# OpenBook_Schematic.net
KiCad netlist of a schematic drawn in EAGLE
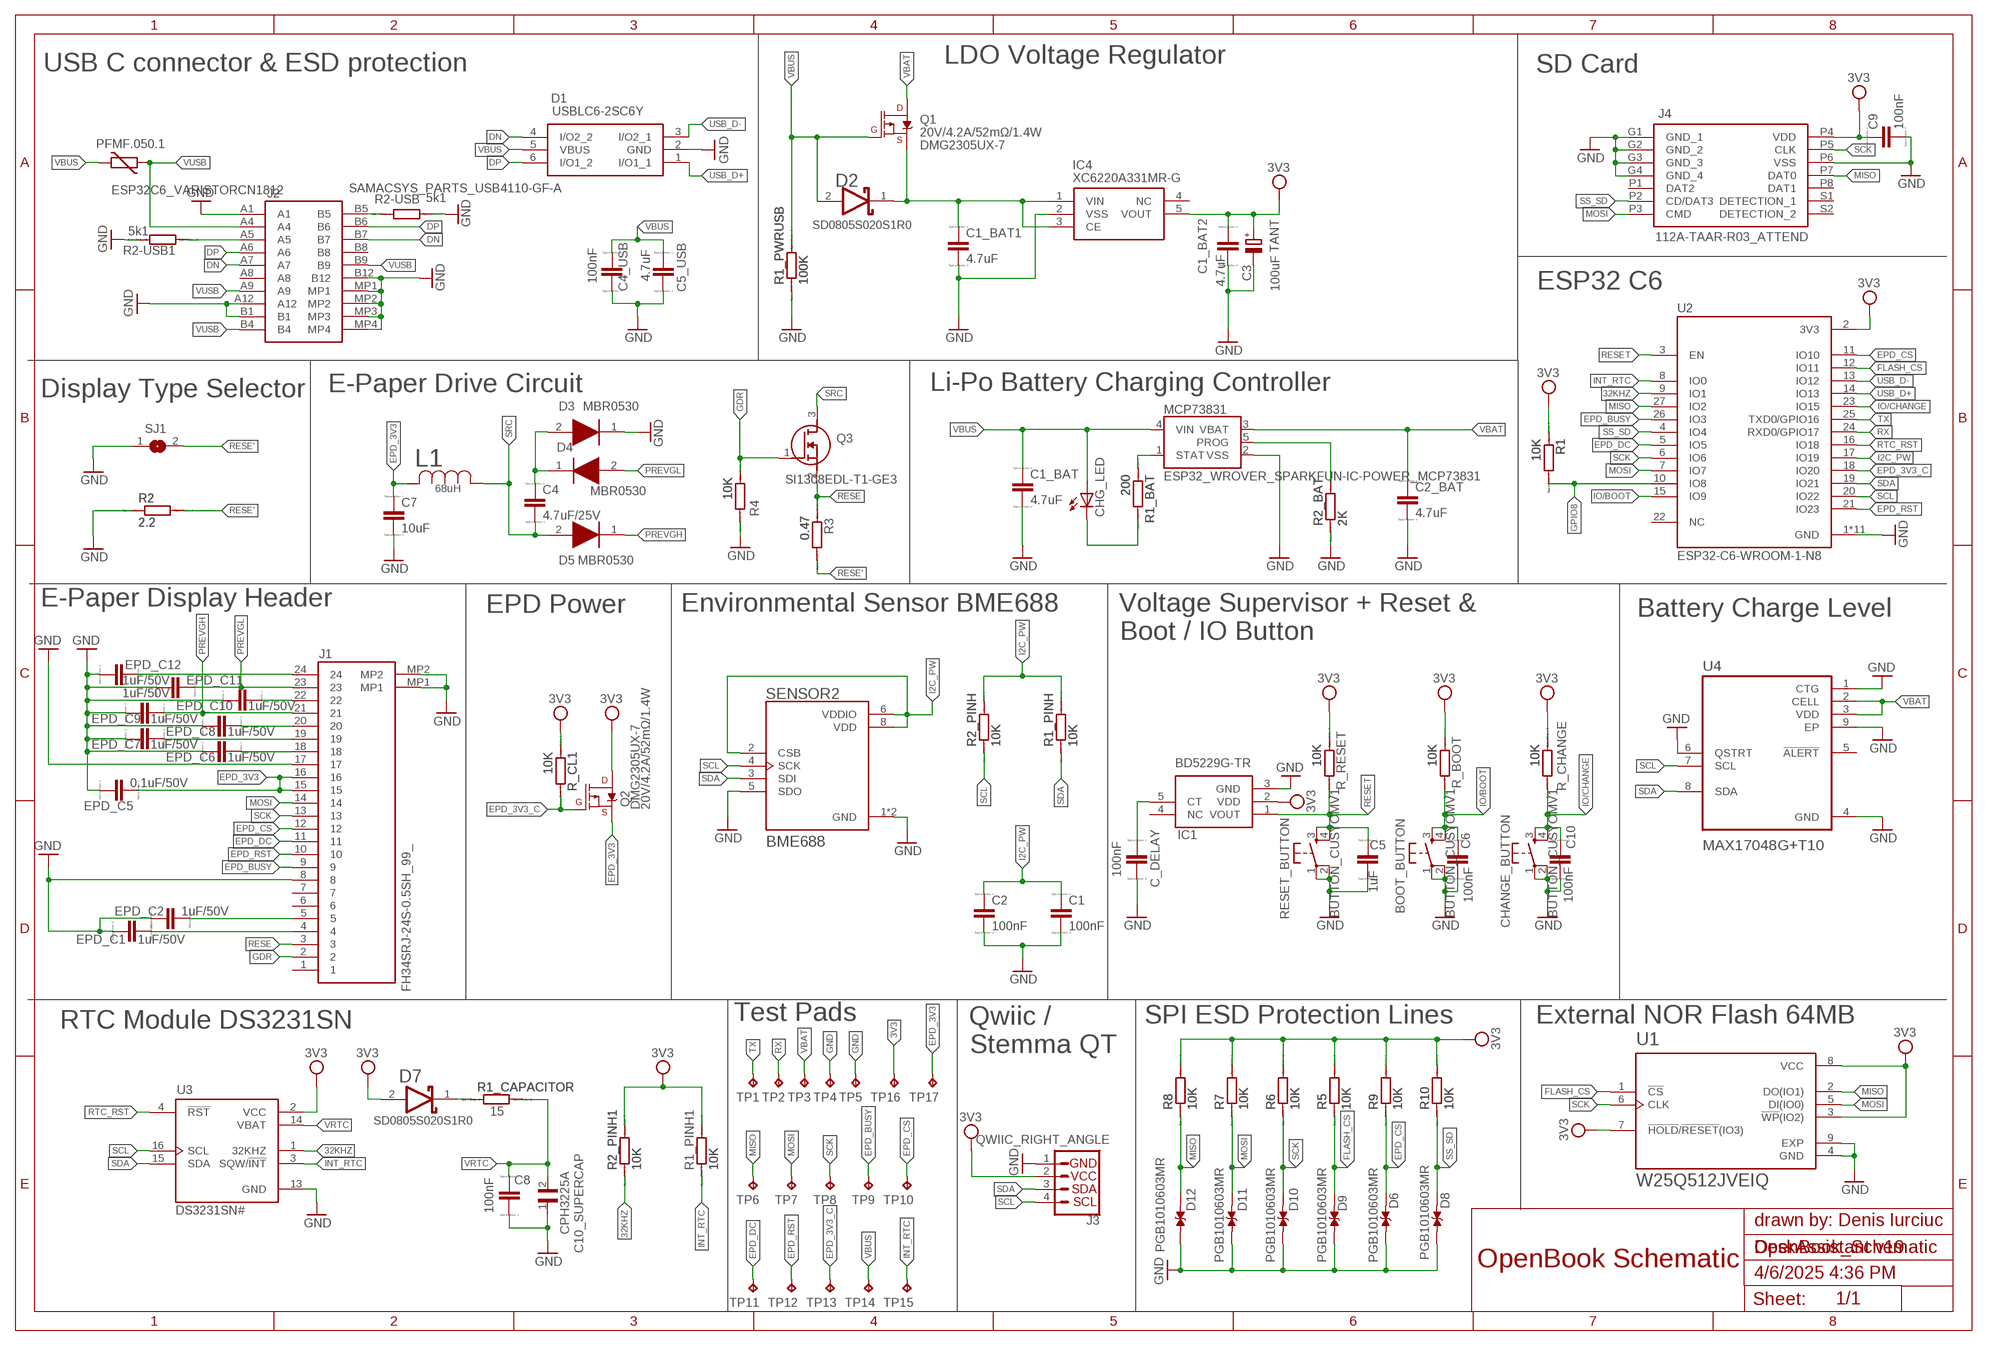
[diagram p0: schematic, sheet 1]

(export (version "E")
  (design (tool "Eeschema 10.0.6"))
  (components
    (comp (ref "BOOT_BUTTON")
      (value "BUTTON_CUSYOMV1")
      (footprint "eagle-import:MYBUTTON")
      (libsource (lib "eagle-import") (part "BUTTON_CUSYOMV1"))
    )
    (comp (ref "C1")
      (value "100nF")
      (footprint "eagle-import:ESP32_WROVER_EAGLE-LTSPICE_C0402")
      (libsource (lib "eagle-import") (part "ESP32_WROVER_EAGLE-LTSPICE_CC0402"))
    )
    (comp (ref "C1_BAT")
      (value "4.7uF")
      (footprint "eagle-import:ESP32_WROVER_EAGLE-LTSPICE_C0402")
      (libsource (lib "eagle-import") (part "ESP32_WROVER_EAGLE-LTSPICE_CC0402"))
    )
    (comp (ref "C1_BAT1")
      (value "4.7uF")
      (footprint "eagle-import:ESP32_WROVER_EAGLE-LTSPICE_C0402")
      (libsource (lib "eagle-import") (part "ESP32_WROVER_EAGLE-LTSPICE_CC0402"))
    )
    (comp (ref "C1_BAT2")
      (value "4.7uF")
      (footprint "eagle-import:ESP32_WROVER_EAGLE-LTSPICE_C0402")
      (libsource (lib "eagle-import") (part "ESP32_WROVER_EAGLE-LTSPICE_CC0402"))
    )
    (comp (ref "C2")
      (value "100nF")
      (footprint "eagle-import:ESP32_WROVER_EAGLE-LTSPICE_C0402")
      (libsource (lib "eagle-import") (part "ESP32_WROVER_EAGLE-LTSPICE_CC0402"))
    )
    (comp (ref "C2_BAT")
      (value "4.7uF")
      (footprint "eagle-import:ESP32_WROVER_EAGLE-LTSPICE_C0402")
      (libsource (lib "eagle-import") (part "ESP32_WROVER_EAGLE-LTSPICE_CC0402"))
    )
    (comp (ref "C3")
      (value "100uF")
      (footprint "eagle-import:RCL_CT3528")
      (fields (field (name "TYPE") "TANT"))
      (libsource (lib "eagle-import") (part "RCL_CPOL-EUCT3528"))
    )
    (comp (ref "C4")
      (value "4.7uF/25V")
      (footprint "eagle-import:ESP32_WROVER_EAGLE-LTSPICE_C0402")
      (libsource (lib "eagle-import") (part "ESP32_WROVER_EAGLE-LTSPICE_CC0402"))
    )
    (comp (ref "C4_USB")
      (value "100nF")
      (footprint "eagle-import:ESP32_WROVER_EAGLE-LTSPICE_C0402")
      (libsource (lib "eagle-import") (part "ESP32_WROVER_EAGLE-LTSPICE_CC0402"))
    )
    (comp (ref "C5")
      (value "1uF")
      (footprint "eagle-import:ESP32_WROVER_EAGLE-LTSPICE_C0402")
      (libsource (lib "eagle-import") (part "ESP32_WROVER_EAGLE-LTSPICE_CC0402"))
    )
    (comp (ref "C5_USB")
      (value "4.7uF")
      (footprint "eagle-import:ESP32_WROVER_EAGLE-LTSPICE_C0402")
      (libsource (lib "eagle-import") (part "ESP32_WROVER_EAGLE-LTSPICE_CC0402"))
    )
    (comp (ref "C6")
      (value "100nF")
      (footprint "eagle-import:ESP32_WROVER_EAGLE-LTSPICE_C0402")
      (libsource (lib "eagle-import") (part "ESP32_WROVER_EAGLE-LTSPICE_CC0402"))
    )
    (comp (ref "C7")
      (value "10uF")
      (footprint "eagle-import:ESP32_WROVER_EAGLE-LTSPICE_C0402")
      (libsource (lib "eagle-import") (part "ESP32_WROVER_EAGLE-LTSPICE_CC0402"))
    )
    (comp (ref "C8")
      (value "100nF")
      (footprint "eagle-import:ESP32_WROVER_EAGLE-LTSPICE_C0402")
      (libsource (lib "eagle-import") (part "ESP32_WROVER_EAGLE-LTSPICE_CC0402"))
    )
    (comp (ref "C9")
      (value "100nF")
      (footprint "eagle-import:ESP32_WROVER_EAGLE-LTSPICE_C0402")
      (libsource (lib "eagle-import") (part "ESP32_WROVER_EAGLE-LTSPICE_CC0402"))
    )
    (comp (ref "C10")
      (value "100nF")
      (footprint "eagle-import:ESP32_WROVER_EAGLE-LTSPICE_C0402")
      (libsource (lib "eagle-import") (part "ESP32_WROVER_EAGLE-LTSPICE_CC0402"))
    )
    (comp (ref "C10_SUPERCAP")
      (value "CPH3225A")
      (footprint "eagle-import:CAPCP3225X100N")
      (fields (field (name "MF") "Seiko Instruments"))
      (libsource (lib "eagle-import") (part "CPH3225A"))
    )
    (comp (ref "CHANGE_BUTTON")
      (value "BUTTON_CUSYOMV1")
      (footprint "eagle-import:MYBUTTON")
      (libsource (lib "eagle-import") (part "BUTTON_CUSYOMV1"))
    )
    (comp (ref "CHG_LED")
      (value "ADAFRUIT_LEDCHIP-LED0603")
      (footprint "eagle-import:ADAFRUIT_CHIP-LED0603")
      (libsource (lib "eagle-import") (part "ADAFRUIT_LEDCHIP-LED0603"))
    )
    (comp (ref "C_DELAY")
      (value "100nF")
      (footprint "eagle-import:ESP32_WROVER_EAGLE-LTSPICE_C0402")
      (libsource (lib "eagle-import") (part "ESP32_WROVER_EAGLE-LTSPICE_CC0402"))
    )
    (comp (ref "D1")
      (value "USBLC6-2SC6Y")
      (footprint "eagle-import:SOT95P280X145-6N")
      (fields (field (name "MF") "STMicroelectronics"))
      (libsource (lib "eagle-import") (part "USBLC6-2SC6Y"))
    )
    (comp (ref "D2")
      (value "ESP32_WROVER_AVX---SD0805S020S1R0_AVX_SD0805S020S1R0_0_0AVX_SD0805S020S1R0_0_0")
      (footprint "eagle-import:ESP32_WROVER_AVX---SD0805S020S1R0_AVX_SD0805S020S1R0_0")
      (fields
        (field (name "DIGIKEY_PART_NUMBER") "478-7800-1-ND")
        (field (name "MF") "AVX")
        (field (name "MOUSER_PART_NUMBER") "581-SD0805S020S1R0")
        (field (name "VALUE_TXT") "SD0805S020S1R0")
      )
      (libsource (lib "eagle-import") (part "ESP32_WROVER_AVX---SD0805S020S1R0_AVX_SD0805S020S1R0_0_0AVX_SD0805S020S1R0_0_0"))
    )
    (comp (ref "D3")
      (value "MBR0530")
      (footprint "eagle-import:SOD3716X135N")
      (fields (field (name "MF") "ON Semiconductor"))
      (libsource (lib "eagle-import") (part "MBR0530"))
    )
    (comp (ref "D4")
      (value "MBR0530")
      (footprint "eagle-import:SOD3716X135N")
      (fields (field (name "MF") "ON Semiconductor"))
      (libsource (lib "eagle-import") (part "MBR0530"))
    )
    (comp (ref "D5")
      (value "MBR0530")
      (footprint "eagle-import:SOD3716X135N")
      (fields (field (name "MF") "ON Semiconductor"))
      (libsource (lib "eagle-import") (part "MBR0530"))
    )
    (comp (ref "D6")
      (value "PGB1010603MR")
      (footprint "eagle-import:DIOC1608X36N")
      (fields (field (name "MF") "Littelfuse Inc."))
      (libsource (lib "eagle-import") (part "PGB1010603MR"))
    )
    (comp (ref "D7")
      (value "SD0805S020S1R0")
      (footprint "eagle-import:ESP32_WROVER_AVX---SD0805S020S1R0_AVX_SD0805S020S1R0_0")
      (fields
        (field (name "DIGIKEY_PART_NUMBER") "478-7800-1-ND")
        (field (name "MF") "AVX")
        (field (name "MOUSER_PART_NUMBER") "581-SD0805S020S1R0")
        (field (name "VALUE_TXT") "SD0805S020S1R0")
      )
      (libsource (lib "eagle-import") (part "ESP32_WROVER_AVX---SD0805S020S1R0_AVX_SD0805S020S1R0_0_0AVX_SD0805S020S1R0_0_0"))
    )
    (comp (ref "D8")
      (value "PGB1010603MR")
      (footprint "eagle-import:DIOC1608X36N")
      (fields (field (name "MF") "Littelfuse Inc."))
      (libsource (lib "eagle-import") (part "PGB1010603MR"))
    )
    (comp (ref "D9")
      (value "PGB1010603MR")
      (footprint "eagle-import:DIOC1608X36N")
      (fields (field (name "MF") "Littelfuse Inc."))
      (libsource (lib "eagle-import") (part "PGB1010603MR"))
    )
    (comp (ref "D10")
      (value "PGB1010603MR")
      (footprint "eagle-import:DIOC1608X36N")
      (fields (field (name "MF") "Littelfuse Inc."))
      (libsource (lib "eagle-import") (part "PGB1010603MR"))
    )
    (comp (ref "D11")
      (value "PGB1010603MR")
      (footprint "eagle-import:DIOC1608X36N")
      (fields (field (name "MF") "Littelfuse Inc."))
      (libsource (lib "eagle-import") (part "PGB1010603MR"))
    )
    (comp (ref "D12")
      (value "PGB1010603MR")
      (footprint "eagle-import:DIOC1608X36N")
      (fields (field (name "MF") "Littelfuse Inc."))
      (libsource (lib "eagle-import") (part "PGB1010603MR"))
    )
    (comp (ref "EPD_C1")
      (value "1uF/50V")
      (footprint "eagle-import:ESP32_WROVER_EAGLE-LTSPICE_C0402")
      (libsource (lib "eagle-import") (part "ESP32_WROVER_EAGLE-LTSPICE_CC0402"))
    )
    (comp (ref "EPD_C2")
      (value "1uF/50V")
      (footprint "eagle-import:ESP32_WROVER_EAGLE-LTSPICE_C0402")
      (libsource (lib "eagle-import") (part "ESP32_WROVER_EAGLE-LTSPICE_CC0402"))
    )
    (comp (ref "EPD_C5")
      (value "0.1uF/50V")
      (footprint "eagle-import:ESP32_WROVER_EAGLE-LTSPICE_C0402")
      (libsource (lib "eagle-import") (part "ESP32_WROVER_EAGLE-LTSPICE_CC0402"))
    )
    (comp (ref "EPD_C6")
      (value "1uF/50V")
      (footprint "eagle-import:ESP32_WROVER_EAGLE-LTSPICE_C0402")
      (libsource (lib "eagle-import") (part "ESP32_WROVER_EAGLE-LTSPICE_CC0402"))
    )
    (comp (ref "EPD_C7")
      (value "1uF/50V")
      (footprint "eagle-import:ESP32_WROVER_EAGLE-LTSPICE_C0402")
      (libsource (lib "eagle-import") (part "ESP32_WROVER_EAGLE-LTSPICE_CC0402"))
    )
    (comp (ref "EPD_C8")
      (value "1uF/50V")
      (footprint "eagle-import:ESP32_WROVER_EAGLE-LTSPICE_C0402")
      (libsource (lib "eagle-import") (part "ESP32_WROVER_EAGLE-LTSPICE_CC0402"))
    )
    (comp (ref "EPD_C9")
      (value "1uF/50V")
      (footprint "eagle-import:ESP32_WROVER_EAGLE-LTSPICE_C0402")
      (libsource (lib "eagle-import") (part "ESP32_WROVER_EAGLE-LTSPICE_CC0402"))
    )
    (comp (ref "EPD_C10")
      (value "1uF/50V")
      (footprint "eagle-import:ESP32_WROVER_EAGLE-LTSPICE_C0402")
      (libsource (lib "eagle-import") (part "ESP32_WROVER_EAGLE-LTSPICE_CC0402"))
    )
    (comp (ref "EPD_C11")
      (value "1uF/50V")
      (footprint "eagle-import:ESP32_WROVER_EAGLE-LTSPICE_C0402")
      (libsource (lib "eagle-import") (part "ESP32_WROVER_EAGLE-LTSPICE_CC0402"))
    )
    (comp (ref "EPD_C12")
      (value "1uF/50V")
      (footprint "eagle-import:ESP32_WROVER_EAGLE-LTSPICE_C0402")
      (libsource (lib "eagle-import") (part "ESP32_WROVER_EAGLE-LTSPICE_CC0402"))
    )
    (comp (ref "IC1")
      (value "BD5229G-TR")
      (footprint "eagle-import:SOT95P280X125-5N")
      (fields (field (name "MOUSER_PART_NUMBER") "755-BD5229G-TR"))
      (libsource (lib "eagle-import") (part "BD5229G-TR"))
    )
    (comp (ref "IC4")
      (value "XC6220A331MR-G")
      (footprint "eagle-import:SOT95P280X120-5N")
      (fields (field (name "MOUSER_PART_NUMBER") "865-XC6220A331MR-G"))
      (libsource (lib "eagle-import") (part "XC6220A331MR-G"))
    )
    (comp (ref "J1")
      (value "FH34SRJ-24S-0.5SH_99_")
      (footprint "eagle-import:FH34SRJ24S05SH99")
      (fields
        (field (name "MANUFACTURER_PART_NUMBER") "FH34SRJ-24S-0.5SH(99)")
        (field (name "MOUSER_PART_NUMBER") "798-FH34SRJ24S05SH99")
      )
      (libsource (lib "eagle-import") (part "FH34SRJ-24S-0.5SH_99_"))
    )
    (comp (ref "J2")
      (value "SAMACSYS_PARTS_USB4110-GF-A")
      (footprint "eagle-import:SAMACSYS_PARTS_USB4110GFA")
      (fields
        (field (name "MANUFACTURER_PART_NUMBER") "USB4110-GF-A")
        (field (name "MOUSER_PART_NUMBER") "640-USB4110-GF-A")
      )
      (libsource (lib "eagle-import") (part "SAMACSYS_PARTS_USB4110-GF-A"))
    )
    (comp (ref "J3")
      (value "QWIIC_RIGHT_ANGLE")
      (footprint "eagle-import:JST04_1MM_RA")
      (libsource (lib "eagle-import") (part "QWIIC_CONNECTORJS-1MM"))
    )
    (comp (ref "J4")
      (value "112A-TAAR-R03_ATTEND")
      (footprint "eagle-import:112ATAARR03ATTEND")
      (fields (field (name "MANUFACTURER_PART_NUMBER") "112A-TAAR-R03 ATTEND"))
      (libsource (lib "eagle-import") (part "112A-TAAR-R03_ATTEND"))
    )
    (comp (ref "L1")
      (value "68uH")
      (footprint "eagle-import:IND_4828-WE-TPC_WRE")
      (fields
        (field (name "MANUFACTURER_PART_NUMBER") "744043680")
        (field (name "COPYRIGHT") "Copyright (C) 2024 Ultra Librarian. All rights reserved.")
      )
      (libsource (lib "eagle-import") (part "744043680IND_4828-WE-TPC_WRE"))
    )
    (comp (ref "MCP73831")
      (value "ESP32_WROVER_SPARKFUN-IC-POWER_MCP73831")
      (footprint "eagle-import:ESP32_WROVER_SPARKFUN-IC-POWER_SOT23-5")
      (libsource (lib "eagle-import") (part "ESP32_WROVER_SPARKFUN-IC-POWER_MCP73831"))
    )
    (comp (ref "PFMF.050.1")
      (value "ESP32C6_VARISTORCN1812")
      (footprint "eagle-import:ESP32C6_VARISTOR_CT_CN1812")
      (libsource (lib "eagle-import") (part "ESP32C6_VARISTORCN1812"))
    )
    (comp (ref "Q1")
      (value "20V/4.2A/52mΩ/1.4W")
      (footprint "eagle-import:ESP32_WROVER_SPARKFUN-DISCRETESEMI_SOT23-3")
      (fields (field (name "P_CHANNEL") "DMG2305UX-7"))
      (libsource (lib "eagle-import") (part "ESP32_WROVER_SPARKFUN-DISCRETESEMI_MOSFET_PCH-DMG2305UX-7"))
    )
    (comp (ref "Q2")
      (value "20V/4.2A/52mΩ/1.4W")
      (footprint "eagle-import:ESP32_WROVER_SPARKFUN-DISCRETESEMI_SOT23-3")
      (fields (field (name "P_CHANNEL") "DMG2305UX-7"))
      (libsource (lib "eagle-import") (part "ESP32_WROVER_SPARKFUN-DISCRETESEMI_MOSFET_PCH-DMG2305UX-7"))
    )
    (comp (ref "Q3")
      (value "SI1308EDL-T1-GE3")
      (footprint "eagle-import:SOT65P210X110-3N")
      (fields (field (name "MF") "Vishay Siliconix"))
      (libsource (lib "eagle-import") (part "SI1308EDL-T1-GE3"))
    )
    (comp (ref "R1")
      (value "10K")
      (footprint "eagle-import:ESP32_WROVER_EAGLE-LTSPICE_R0402")
      (libsource (lib "eagle-import") (part "ESP32_WROVER_EAGLE-LTSPICE_RR0402"))
    )
    (comp (ref "R1_BAT")
      (value "200")
      (footprint "eagle-import:ESP32_WROVER_EAGLE-LTSPICE_R0402")
      (libsource (lib "eagle-import") (part "ESP32_WROVER_EAGLE-LTSPICE_RR0402"))
    )
    (comp (ref "R1_CAPACITOR")
      (value "15")
      (footprint "eagle-import:ESP32_WROVER_EAGLE-LTSPICE_R0402")
      (libsource (lib "eagle-import") (part "ESP32_WROVER_EAGLE-LTSPICE_RR0402"))
    )
    (comp (ref "R1_PINH")
      (value "10K")
      (footprint "eagle-import:ESP32_WROVER_EAGLE-LTSPICE_R0402")
      (libsource (lib "eagle-import") (part "ESP32_WROVER_EAGLE-LTSPICE_RR0402"))
    )
    (comp (ref "R1_PINH1")
      (value "10K")
      (footprint "eagle-import:ESP32_WROVER_EAGLE-LTSPICE_R0402")
      (libsource (lib "eagle-import") (part "ESP32_WROVER_EAGLE-LTSPICE_RR0402"))
    )
    (comp (ref "R1_PWRUSB")
      (value "100K")
      (footprint "eagle-import:ESP32_WROVER_EAGLE-LTSPICE_R0402")
      (libsource (lib "eagle-import") (part "ESP32_WROVER_EAGLE-LTSPICE_RR0402"))
    )
    (comp (ref "R2")
      (value "2.2")
      (footprint "eagle-import:ESP32_WROVER_EAGLE-LTSPICE_R0402")
      (libsource (lib "eagle-import") (part "ESP32_WROVER_EAGLE-LTSPICE_RR0402"))
    )
    (comp (ref "R2-USB")
      (value "5k1")
      (footprint "eagle-import:ESP32_WROVER_EAGLE-LTSPICE_R0402")
      (libsource (lib "eagle-import") (part "ESP32_WROVER_EAGLE-LTSPICE_RR0402"))
    )
    (comp (ref "R2-USB1")
      (value "5k1")
      (footprint "eagle-import:ESP32_WROVER_EAGLE-LTSPICE_R0402")
      (libsource (lib "eagle-import") (part "ESP32_WROVER_EAGLE-LTSPICE_RR0402"))
    )
    (comp (ref "R2_BAT")
      (value "2K")
      (footprint "eagle-import:ESP32_WROVER_EAGLE-LTSPICE_R0402")
      (libsource (lib "eagle-import") (part "ESP32_WROVER_EAGLE-LTSPICE_RR0402"))
    )
    (comp (ref "R2_PINH")
      (value "10K")
      (footprint "eagle-import:ESP32_WROVER_EAGLE-LTSPICE_R0402")
      (libsource (lib "eagle-import") (part "ESP32_WROVER_EAGLE-LTSPICE_RR0402"))
    )
    (comp (ref "R2_PINH1")
      (value "10K")
      (footprint "eagle-import:ESP32_WROVER_EAGLE-LTSPICE_R0402")
      (libsource (lib "eagle-import") (part "ESP32_WROVER_EAGLE-LTSPICE_RR0402"))
    )
    (comp (ref "R3")
      (value "0.47")
      (footprint "eagle-import:ESP32_WROVER_EAGLE-LTSPICE_R0402")
      (libsource (lib "eagle-import") (part "ESP32_WROVER_EAGLE-LTSPICE_RR0402"))
    )
    (comp (ref "R4")
      (value "10K")
      (footprint "eagle-import:ESP32_WROVER_EAGLE-LTSPICE_R0402")
      (libsource (lib "eagle-import") (part "ESP32_WROVER_EAGLE-LTSPICE_RR0402"))
    )
    (comp (ref "R5")
      (value "10K")
      (footprint "eagle-import:ESP32_WROVER_EAGLE-LTSPICE_R0402")
      (libsource (lib "eagle-import") (part "ESP32_WROVER_EAGLE-LTSPICE_RR0402"))
    )
    (comp (ref "R6")
      (value "10K")
      (footprint "eagle-import:ESP32_WROVER_EAGLE-LTSPICE_R0402")
      (libsource (lib "eagle-import") (part "ESP32_WROVER_EAGLE-LTSPICE_RR0402"))
    )
    (comp (ref "R7")
      (value "10K")
      (footprint "eagle-import:ESP32_WROVER_EAGLE-LTSPICE_R0402")
      (libsource (lib "eagle-import") (part "ESP32_WROVER_EAGLE-LTSPICE_RR0402"))
    )
    (comp (ref "R8")
      (value "10K")
      (footprint "eagle-import:ESP32_WROVER_EAGLE-LTSPICE_R0402")
      (libsource (lib "eagle-import") (part "ESP32_WROVER_EAGLE-LTSPICE_RR0402"))
    )
    (comp (ref "R9")
      (value "10K")
      (footprint "eagle-import:ESP32_WROVER_EAGLE-LTSPICE_R0402")
      (libsource (lib "eagle-import") (part "ESP32_WROVER_EAGLE-LTSPICE_RR0402"))
    )
    (comp (ref "R10")
      (value "10K")
      (footprint "eagle-import:ESP32_WROVER_EAGLE-LTSPICE_R0402")
      (libsource (lib "eagle-import") (part "ESP32_WROVER_EAGLE-LTSPICE_RR0402"))
    )
    (comp (ref "RESET_BUTTON")
      (value "BUTTON_CUSYOMV1")
      (footprint "eagle-import:MYBUTTON")
      (libsource (lib "eagle-import") (part "BUTTON_CUSYOMV1"))
    )
    (comp (ref "R_BOOT")
      (value "10K")
      (footprint "eagle-import:ESP32_WROVER_EAGLE-LTSPICE_R0402")
      (libsource (lib "eagle-import") (part "ESP32_WROVER_EAGLE-LTSPICE_RR0402"))
    )
    (comp (ref "R_CHANGE")
      (value "10K")
      (footprint "eagle-import:ESP32_WROVER_EAGLE-LTSPICE_R0402")
      (libsource (lib "eagle-import") (part "ESP32_WROVER_EAGLE-LTSPICE_RR0402"))
    )
    (comp (ref "R_CL1")
      (value "10K")
      (footprint "eagle-import:ESP32_WROVER_EAGLE-LTSPICE_R0402")
      (libsource (lib "eagle-import") (part "ESP32_WROVER_EAGLE-LTSPICE_RR0402"))
    )
    (comp (ref "R_RESET")
      (value "10K")
      (footprint "eagle-import:ESP32_WROVER_EAGLE-LTSPICE_R0402")
      (libsource (lib "eagle-import") (part "ESP32_WROVER_EAGLE-LTSPICE_RR0402"))
    )
    (comp (ref "SENSOR2")
      (value "BME688")
      (footprint "eagle-import:ESP32_WROVER_BME680_PSON80P300X300X100-8N")
      (fields (field (name "MF") "Bosch Sensortec") (field (name "MP") "BME680"))
      (libsource (lib "eagle-import") (part "ESP32_WROVER_BME680_BME680"))
    )
    (comp (ref "SJ1") (value "SJ") (footprint "eagle-import:SJ") (libsource (lib "eagle-import") (part "SJ")))
    (comp (ref "TP1")
      (value "TPTP20R")
      (footprint "eagle-import:TP20R")
      (libsource (lib "eagle-import") (part "TPTP20R"))
    )
    (comp (ref "TP2")
      (value "TPTP20R")
      (footprint "eagle-import:TP20R")
      (libsource (lib "eagle-import") (part "TPTP20R"))
    )
    (comp (ref "TP3")
      (value "TPTP20R")
      (footprint "eagle-import:TP20R")
      (libsource (lib "eagle-import") (part "TPTP20R"))
    )
    (comp (ref "TP4")
      (value "TPTP20R")
      (footprint "eagle-import:TP20R")
      (libsource (lib "eagle-import") (part "TPTP20R"))
    )
    (comp (ref "TP5")
      (value "TPTP20R")
      (footprint "eagle-import:TP20R")
      (libsource (lib "eagle-import") (part "TPTP20R"))
    )
    (comp (ref "TP6")
      (value "TPTP20R")
      (footprint "eagle-import:TP20R")
      (libsource (lib "eagle-import") (part "TPTP20R"))
    )
    (comp (ref "TP7")
      (value "TPTP20R")
      (footprint "eagle-import:TP20R")
      (libsource (lib "eagle-import") (part "TPTP20R"))
    )
    (comp (ref "TP8")
      (value "TPTP20R")
      (footprint "eagle-import:TP20R")
      (libsource (lib "eagle-import") (part "TPTP20R"))
    )
    (comp (ref "TP9")
      (value "TPTP20R")
      (footprint "eagle-import:TP20R")
      (libsource (lib "eagle-import") (part "TPTP20R"))
    )
    (comp (ref "TP10")
      (value "TPTP20R")
      (footprint "eagle-import:TP20R")
      (libsource (lib "eagle-import") (part "TPTP20R"))
    )
    (comp (ref "TP11")
      (value "TPTP20R")
      (footprint "eagle-import:TP20R")
      (libsource (lib "eagle-import") (part "TPTP20R"))
    )
    (comp (ref "TP12")
      (value "TPTP20R")
      (footprint "eagle-import:TP20R")
      (libsource (lib "eagle-import") (part "TPTP20R"))
    )
    (comp (ref "TP13")
      (value "TPTP20R")
      (footprint "eagle-import:TP20R")
      (libsource (lib "eagle-import") (part "TPTP20R"))
    )
    (comp (ref "TP14")
      (value "TPTP20R")
      (footprint "eagle-import:TP20R")
      (libsource (lib "eagle-import") (part "TPTP20R"))
    )
    (comp (ref "TP15")
      (value "TPTP20R")
      (footprint "eagle-import:TP20R")
      (libsource (lib "eagle-import") (part "TPTP20R"))
    )
    (comp (ref "TP16")
      (value "TPTP20R")
      (footprint "eagle-import:TP20R")
      (libsource (lib "eagle-import") (part "TPTP20R"))
    )
    (comp (ref "TP17")
      (value "TPTP20R")
      (footprint "eagle-import:TP20R")
      (libsource (lib "eagle-import") (part "TPTP20R"))
    )
    (comp (ref "U1")
      (value "W25Q512JVEIQ")
      (footprint "eagle-import:SON127P600X800X80-9N")
      (fields (field (name "MF") "Winbond Electronics"))
      (libsource (lib "eagle-import") (part "W25Q512JVEIQ"))
    )
    (comp (ref "U2")
      (value "ESP32-C6-WROOM-1-N8")
      (footprint "eagle-import:XCVR_ESP32-C6-WROOM-1-N8")
      (fields (field (name "MF") "Espressif Systems"))
      (libsource (lib "eagle-import") (part "ESP32-C6-WROOM-1-N8"))
    )
    (comp (ref "U3")
      (value "DS3231SN#")
      (footprint "eagle-import:SOIC127P1032X265-16N")
      (fields (field (name "MF") "Analog Devices"))
      (libsource (lib "eagle-import") (part "DS3231SN#"))
    )
    (comp (ref "U4")
      (value "MAX17048G+T10")
      (footprint "eagle-import:SON50P200X200X80-9N")
      (fields (field (name "MF") "Analog Devices"))
      (libsource (lib "eagle-import") (part "MAX17048G+T10"))
    )
  )
  (nets
    (net (code "1") (name "3V3") (class "Default")
      (node (ref "C1_BAT2") (pin "1") (pinfunction "1_1") (pintype "passive"))
      (node (ref "C3") (pin "+") (pinfunction "+_+") (pintype "passive"))
      (node (ref "C9") (pin "1") (pinfunction "1_1") (pintype "passive"))
      (node (ref "D7") (pin "2") (pinfunction "ANODE_2") (pintype "bidirectional"))
      (node (ref "IC1") (pin "2") (pinfunction "VDD_2") (pintype "bidirectional"))
      (node (ref "IC4") (pin "5") (pinfunction "VOUT_5") (pintype "bidirectional"))
      (node (ref "J3") (pin "2") (pinfunction "2_2") (pintype "power_in"))
      (node (ref "J4") (pin "P4") (pinfunction "VDD_P4") (pintype "bidirectional"))
      (node (ref "Q2") (pin "3") (pinfunction "D_3") (pintype "bidirectional"))
      (node (ref "R1") (pin "1") (pinfunction "1_1") (pintype "passive"))
      (node (ref "R10") (pin "2") (pinfunction "2_2") (pintype "passive"))
      (node (ref "R1_PINH1") (pin "2") (pinfunction "2_2") (pintype "passive"))
      (node (ref "R2_PINH1") (pin "2") (pinfunction "2_2") (pintype "passive"))
      (node (ref "R5") (pin "2") (pinfunction "2_2") (pintype "passive"))
      (node (ref "R6") (pin "2") (pinfunction "2_2") (pintype "passive"))
      (node (ref "R7") (pin "2") (pinfunction "2_2") (pintype "passive"))
      (node (ref "R8") (pin "2") (pinfunction "2_2") (pintype "passive"))
      (node (ref "R9") (pin "2") (pinfunction "2_2") (pintype "passive"))
      (node (ref "R_BOOT") (pin "1") (pinfunction "1_1") (pintype "passive"))
      (node (ref "R_CHANGE") (pin "1") (pinfunction "1_1") (pintype "passive"))
      (node (ref "R_CL1") (pin "1") (pinfunction "1_1") (pintype "passive"))
      (node (ref "R_RESET") (pin "1") (pinfunction "1_1") (pintype "passive"))
      (node (ref "TP16") (pin "TP") (pinfunction "TP_TP") (pintype "input"))
      (node (ref "U1") (pin "3") (pinfunction "~{WP}(IO2)_3") (pintype "bidirectional"))
      (node (ref "U1") (pin "7") (pinfunction "~{HOLD}/~{RESET}(IO3)_7") (pintype "bidirectional"))
      (node (ref "U1") (pin "8") (pinfunction "VCC_8") (pintype "power_in"))
      (node (ref "U2") (pin "2") (pinfunction "3V3_2") (pintype "power_in"))
      (node (ref "U3") (pin "2") (pinfunction "VCC_2") (pintype "power_in"))
    )
    (net (code "2") (name "32KHZ") (class "Default")
      (node (ref "R2_PINH1") (pin "1") (pinfunction "1_1") (pintype "passive"))
      (node (ref "U2") (pin "9") (pinfunction "IO1_9") (pintype "bidirectional"))
      (node (ref "U3") (pin "1") (pinfunction "32KHZ_1") (pintype "output"))
    )
    (net (code "3") (name "DN") (class "Default")
      (node (ref "D1") (pin "4") (pinfunction "I/O2_2_4") (pintype "bidirectional"))
      (node (ref "J2") (pin "A7") (pinfunction "A7_A7") (pintype "bidirectional"))
      (node (ref "J2") (pin "B7") (pinfunction "B7_B7") (pintype "bidirectional"))
    )
    (net (code "4") (name "DP") (class "Default")
      (node (ref "D1") (pin "6") (pinfunction "I/O1_2_6") (pintype "bidirectional"))
      (node (ref "J2") (pin "A6") (pinfunction "A6_A6") (pintype "bidirectional"))
      (node (ref "J2") (pin "B6") (pinfunction "B6_B6") (pintype "bidirectional"))
    )
    (net (code "5") (name "EPD_3V3") (class "Default")
      (node (ref "C7") (pin "1") (pinfunction "1_1") (pintype "passive"))
      (node (ref "EPD_C5") (pin "1") (pinfunction "1_1") (pintype "passive"))
      (node (ref "J1") (pin "15") (pinfunction "15_15") (pintype "bidirectional"))
      (node (ref "J1") (pin "16") (pinfunction "16_16") (pintype "bidirectional"))
      (node (ref "L1") (pin "2") (pinfunction "2_2") (pintype "passive"))
      (node (ref "Q2") (pin "2") (pinfunction "S_2") (pintype "bidirectional"))
      (node (ref "TP17") (pin "TP") (pinfunction "TP_TP") (pintype "input"))
    )
    (net (code "6") (name "EPD_3V3_C") (class "Default")
      (node (ref "Q2") (pin "1") (pinfunction "G_1") (pintype "bidirectional"))
      (node (ref "R_CL1") (pin "2") (pinfunction "2_2") (pintype "passive"))
      (node (ref "TP13") (pin "TP") (pinfunction "TP_TP") (pintype "input"))
      (node (ref "U2") (pin "18") (pinfunction "IO20_18") (pintype "bidirectional"))
    )
    (net (code "7") (name "EPD_BUSY") (class "Default")
      (node (ref "J1") (pin "9") (pinfunction "9_9") (pintype "bidirectional"))
      (node (ref "TP9") (pin "TP") (pinfunction "TP_TP") (pintype "input"))
      (node (ref "U2") (pin "26") (pinfunction "IO3_26") (pintype "bidirectional"))
    )
    (net (code "8") (name "EPD_CS") (class "Default")
      (node (ref "D6") (pin "2") (pinfunction "2_2") (pintype "passive"))
      (node (ref "J1") (pin "12") (pinfunction "12_12") (pintype "bidirectional"))
      (node (ref "R9") (pin "1") (pinfunction "1_1") (pintype "passive"))
      (node (ref "TP10") (pin "TP") (pinfunction "TP_TP") (pintype "input"))
      (node (ref "U2") (pin "11") (pinfunction "IO10_11") (pintype "bidirectional"))
    )
    (net (code "9") (name "EPD_DC") (class "Default")
      (node (ref "J1") (pin "11") (pinfunction "11_11") (pintype "bidirectional"))
      (node (ref "TP11") (pin "TP") (pinfunction "TP_TP") (pintype "input"))
      (node (ref "U2") (pin "5") (pinfunction "IO5_5") (pintype "bidirectional"))
    )
    (net (code "10") (name "EPD_RST") (class "Default")
      (node (ref "J1") (pin "10") (pinfunction "10_10") (pintype "bidirectional"))
      (node (ref "TP12") (pin "TP") (pinfunction "TP_TP") (pintype "input"))
      (node (ref "U2") (pin "21") (pinfunction "IO23_21") (pintype "bidirectional"))
    )
    (net (code "11") (name "FLASH_CS") (class "Default")
      (node (ref "D9") (pin "2") (pinfunction "2_2") (pintype "passive"))
      (node (ref "R5") (pin "1") (pinfunction "1_1") (pintype "passive"))
      (node (ref "U1") (pin "1") (pinfunction "~{CS}_1") (pintype "input"))
      (node (ref "U2") (pin "12") (pinfunction "IO11_12") (pintype "bidirectional"))
    )
    (net (code "12") (name "GDR") (class "Default")
      (node (ref "J1") (pin "2") (pinfunction "2_2") (pintype "bidirectional"))
      (node (ref "Q3") (pin "1") (pinfunction "G_1") (pintype "bidirectional"))
      (node (ref "R4") (pin "1") (pinfunction "1_1") (pintype "passive"))
    )
    (net (code "13") (name "GND") (class "Default")
      (node (ref "BOOT_BUTTON") (pin "1") (pinfunction "1_1") (pintype "passive"))
      (node (ref "BOOT_BUTTON") (pin "2") (pinfunction "2_2") (pintype "passive"))
      (node (ref "C1") (pin "2") (pinfunction "2_2") (pintype "passive"))
      (node (ref "C10") (pin "2") (pinfunction "2_2") (pintype "passive"))
      (node (ref "C10_SUPERCAP") (pin "1") (pinfunction "1_1") (pintype "passive"))
      (node (ref "C1_BAT") (pin "2") (pinfunction "2_2") (pintype "passive"))
      (node (ref "C1_BAT1") (pin "2") (pinfunction "2_2") (pintype "passive"))
      (node (ref "C1_BAT2") (pin "2") (pinfunction "2_2") (pintype "passive"))
      (node (ref "C2") (pin "2") (pinfunction "2_2") (pintype "passive"))
      (node (ref "C2_BAT") (pin "2") (pinfunction "2_2") (pintype "passive"))
      (node (ref "C3") (pin "-") (pinfunction "-_-") (pintype "passive"))
      (node (ref "C4_USB") (pin "2") (pinfunction "2_2") (pintype "passive"))
      (node (ref "C5") (pin "2") (pinfunction "2_2") (pintype "passive"))
      (node (ref "C5_USB") (pin "2") (pinfunction "2_2") (pintype "passive"))
      (node (ref "C6") (pin "2") (pinfunction "2_2") (pintype "passive"))
      (node (ref "C7") (pin "2") (pinfunction "2_2") (pintype "passive"))
      (node (ref "C8") (pin "2") (pinfunction "2_2") (pintype "passive"))
      (node (ref "C9") (pin "2") (pinfunction "2_2") (pintype "passive"))
      (node (ref "CHANGE_BUTTON") (pin "1") (pinfunction "1_1") (pintype "passive"))
      (node (ref "CHANGE_BUTTON") (pin "2") (pinfunction "2_2") (pintype "passive"))
      (node (ref "C_DELAY") (pin "2") (pinfunction "2_2") (pintype "passive"))
      (node (ref "D1") (pin "2") (pinfunction "GND_2") (pintype "bidirectional"))
      (node (ref "D10") (pin "1") (pinfunction "1_1") (pintype "passive"))
      (node (ref "D11") (pin "1") (pinfunction "1_1") (pintype "passive"))
      (node (ref "D12") (pin "1") (pinfunction "1_1") (pintype "passive"))
      (node (ref "D3") (pin "1") (pinfunction "K_1") (pintype "bidirectional"))
      (node (ref "D6") (pin "1") (pinfunction "1_1") (pintype "passive"))
      (node (ref "D8") (pin "1") (pinfunction "1_1") (pintype "passive"))
      (node (ref "D9") (pin "1") (pinfunction "1_1") (pintype "passive"))
      (node (ref "EPD_C1") (pin "2") (pinfunction "2_2") (pintype "passive"))
      (node (ref "EPD_C10") (pin "2") (pinfunction "2_2") (pintype "passive"))
      (node (ref "EPD_C11") (pin "2") (pinfunction "2_2") (pintype "passive"))
      (node (ref "EPD_C12") (pin "2") (pinfunction "2_2") (pintype "passive"))
      (node (ref "EPD_C2") (pin "2") (pinfunction "2_2") (pintype "passive"))
      (node (ref "EPD_C5") (pin "2") (pinfunction "2_2") (pintype "passive"))
      (node (ref "EPD_C6") (pin "2") (pinfunction "2_2") (pintype "passive"))
      (node (ref "EPD_C7") (pin "2") (pinfunction "2_2") (pintype "passive"))
      (node (ref "EPD_C8") (pin "2") (pinfunction "2_2") (pintype "passive"))
      (node (ref "EPD_C9") (pin "2") (pinfunction "2_2") (pintype "passive"))
      (node (ref "IC1") (pin "3") (pinfunction "GND_3") (pintype "bidirectional"))
      (node (ref "IC4") (pin "2") (pinfunction "VSS_2") (pintype "bidirectional"))
      (node (ref "J1") (pin "17") (pinfunction "17_17") (pintype "bidirectional"))
      (node (ref "J1") (pin "8") (pinfunction "8_8") (pintype "bidirectional"))
      (node (ref "J1") (pin "MP1") (pinfunction "MP1_MP1") (pintype "bidirectional"))
      (node (ref "J1") (pin "MP2") (pinfunction "MP2_MP2") (pintype "bidirectional"))
      (node (ref "J2") (pin "A1") (pinfunction "A1_A1") (pintype "bidirectional"))
      (node (ref "J2") (pin "A12") (pinfunction "A12_A12") (pintype "bidirectional"))
      (node (ref "J2") (pin "B1") (pinfunction "B1_B1") (pintype "bidirectional"))
      (node (ref "J2") (pin "B12") (pinfunction "B12_B12") (pintype "bidirectional"))
      (node (ref "J2") (pin "MP1") (pinfunction "MP1_MP1") (pintype "bidirectional"))
      (node (ref "J2") (pin "MP2") (pinfunction "MP2_MP2") (pintype "bidirectional"))
      (node (ref "J2") (pin "MP3") (pinfunction "MP3_MP3") (pintype "bidirectional"))
      (node (ref "J2") (pin "MP4") (pinfunction "MP4_MP4") (pintype "bidirectional"))
      (node (ref "J3") (pin "1") (pinfunction "1_1") (pintype "power_in"))
      (node (ref "J4") (pin "G1") (pinfunction "GND_1_G1") (pintype "bidirectional"))
      (node (ref "J4") (pin "G2") (pinfunction "GND_2_G2") (pintype "bidirectional"))
      (node (ref "J4") (pin "G3") (pinfunction "GND_3_G3") (pintype "bidirectional"))
      (node (ref "J4") (pin "G4") (pinfunction "GND_4_G4") (pintype "bidirectional"))
      (node (ref "J4") (pin "P6") (pinfunction "VSS_P6") (pintype "bidirectional"))
      (node (ref "MCP73831") (pin "2") (pinfunction "VSS_2") (pintype "power_in"))
      (node (ref "R1_PWRUSB") (pin "1") (pinfunction "1_1") (pintype "passive"))
      (node (ref "R2") (pin "1") (pinfunction "1_1") (pintype "passive"))
      (node (ref "R2-USB") (pin "2") (pinfunction "2_2") (pintype "passive"))
      (node (ref "R2-USB1") (pin "1") (pinfunction "1_1") (pintype "passive"))
      (node (ref "R2_BAT") (pin "1") (pinfunction "1_1") (pintype "passive"))
      (node (ref "R4") (pin "2") (pinfunction "2_2") (pintype "passive"))
      (node (ref "RESET_BUTTON") (pin "1") (pinfunction "1_1") (pintype "passive"))
      (node (ref "RESET_BUTTON") (pin "2") (pinfunction "2_2") (pintype "passive"))
      (node (ref "SENSOR2") (pin "1") (pinfunction "GND_1") (pintype "power_in"))
      (node (ref "SENSOR2") (pin "5") (pinfunction "SDO_5") (pintype "bidirectional"))
      (node (ref "SENSOR2") (pin "7") (pinfunction "GND_7") (pintype "power_in"))
      (node (ref "SJ1") (pin "1") (pinfunction "1_1") (pintype "passive"))
      (node (ref "TP4") (pin "TP") (pinfunction "TP_TP") (pintype "input"))
      (node (ref "TP5") (pin "TP") (pinfunction "TP_TP") (pintype "input"))
      (node (ref "U1") (pin "4") (pinfunction "GND_4") (pintype "power_in"))
      (node (ref "U1") (pin "9") (pinfunction "EXP_9") (pintype "passive"))
      (node (ref "U2") (pin "1") (pinfunction "GND_1") (pintype "power_in"))
      (node (ref "U2") (pin "28") (pinfunction "GND_28") (pintype "power_in"))
      (node (ref "U2") (pin "29_1") (pinfunction "GND_29_1") (pintype "power_in"))
      (node (ref "U2") (pin "29_2") (pinfunction "GND_29_2") (pintype "power_in"))
      (node (ref "U2") (pin "29_3") (pinfunction "GND_29_3") (pintype "power_in"))
      (node (ref "U2") (pin "29_4") (pinfunction "GND_29_4") (pintype "power_in"))
      (node (ref "U2") (pin "29_5") (pinfunction "GND_29_5") (pintype "power_in"))
      (node (ref "U2") (pin "29_6") (pinfunction "GND_29_6") (pintype "power_in"))
      (node (ref "U2") (pin "29_7") (pinfunction "GND_29_7") (pintype "power_in"))
      (node (ref "U2") (pin "29_8") (pinfunction "GND_29_8") (pintype "power_in"))
      (node (ref "U2") (pin "29_9") (pinfunction "GND_29_9") (pintype "power_in"))
      (node (ref "U3") (pin "13") (pinfunction "GND_13") (pintype "power_in"))
      (node (ref "U4") (pin "1") (pinfunction "CTG_1") (pintype "power_in"))
      (node (ref "U4") (pin "4") (pinfunction "GND_4") (pintype "power_in"))
      (node (ref "U4") (pin "6") (pinfunction "QSTRT_6") (pintype "input"))
      (node (ref "U4") (pin "9") (pinfunction "EP_9") (pintype "power_in"))
    )
    (net (code "14") (name "GPIO8") (class "Default")
      (node (ref "R1") (pin "2") (pinfunction "2_2") (pintype "passive"))
      (node (ref "U2") (pin "10") (pinfunction "IO8_10") (pintype "bidirectional"))
    )
    (net (code "15") (name "I2C_PW") (class "Default")
      (node (ref "C1") (pin "1") (pinfunction "1_1") (pintype "passive"))
      (node (ref "C2") (pin "1") (pinfunction "1_1") (pintype "passive"))
      (node (ref "R1_PINH") (pin "2") (pinfunction "2_2") (pintype "passive"))
      (node (ref "R2_PINH") (pin "2") (pinfunction "2_2") (pintype "passive"))
      (node (ref "SENSOR2") (pin "2") (pinfunction "CSB_2") (pintype "input"))
      (node (ref "SENSOR2") (pin "6") (pinfunction "VDDIO_6") (pintype "power_in"))
      (node (ref "SENSOR2") (pin "8") (pinfunction "VDD_8") (pintype "power_in"))
      (node (ref "U2") (pin "17") (pinfunction "IO19_17") (pintype "bidirectional"))
    )
    (net (code "16") (name "INT_RTC") (class "Default")
      (node (ref "R1_PINH1") (pin "1") (pinfunction "1_1") (pintype "passive"))
      (node (ref "TP15") (pin "TP") (pinfunction "TP_TP") (pintype "input"))
      (node (ref "U2") (pin "8") (pinfunction "IO0_8") (pintype "bidirectional"))
      (node (ref "U3") (pin "3") (pinfunction "SQW/~{INT}_3") (pintype "output"))
    )
    (net (code "17") (name "IO{slash}BOOT") (class "Default")
      (node (ref "BOOT_BUTTON") (pin "3") (pinfunction "3_3") (pintype "passive"))
      (node (ref "BOOT_BUTTON") (pin "4") (pinfunction "4_4") (pintype "passive"))
      (node (ref "C6") (pin "1") (pinfunction "1_1") (pintype "passive"))
      (node (ref "R_BOOT") (pin "2") (pinfunction "2_2") (pintype "passive"))
      (node (ref "U2") (pin "15") (pinfunction "IO9_15") (pintype "bidirectional"))
    )
    (net (code "18") (name "IO{slash}CHANGE") (class "Default")
      (node (ref "C10") (pin "1") (pinfunction "1_1") (pintype "passive"))
      (node (ref "CHANGE_BUTTON") (pin "3") (pinfunction "3_3") (pintype "passive"))
      (node (ref "CHANGE_BUTTON") (pin "4") (pinfunction "4_4") (pintype "passive"))
      (node (ref "R_CHANGE") (pin "2") (pinfunction "2_2") (pintype "passive"))
      (node (ref "U2") (pin "23") (pinfunction "IO15_23") (pintype "bidirectional"))
    )
    (net (code "19") (name "MISO") (class "Default")
      (node (ref "D12") (pin "2") (pinfunction "2_2") (pintype "passive"))
      (node (ref "J4") (pin "P7") (pinfunction "DAT0_P7") (pintype "bidirectional"))
      (node (ref "R8") (pin "1") (pinfunction "1_1") (pintype "passive"))
      (node (ref "TP6") (pin "TP") (pinfunction "TP_TP") (pintype "input"))
      (node (ref "U1") (pin "2") (pinfunction "DO(IO1)_2") (pintype "bidirectional"))
      (node (ref "U2") (pin "27") (pinfunction "IO2_27") (pintype "bidirectional"))
    )
    (net (code "20") (name "MOSI") (class "Default")
      (node (ref "D11") (pin "2") (pinfunction "2_2") (pintype "passive"))
      (node (ref "J1") (pin "14") (pinfunction "14_14") (pintype "bidirectional"))
      (node (ref "J4") (pin "P3") (pinfunction "CMD_P3") (pintype "bidirectional"))
      (node (ref "R7") (pin "1") (pinfunction "1_1") (pintype "passive"))
      (node (ref "TP7") (pin "TP") (pinfunction "TP_TP") (pintype "input"))
      (node (ref "U1") (pin "5") (pinfunction "DI(IO0)_5") (pintype "bidirectional"))
      (node (ref "U2") (pin "7") (pinfunction "IO7_7") (pintype "bidirectional"))
    )
    (net (code "21") (name "Net-(CHG_LED-PadC)") (class "Default")
      (node (ref "CHG_LED") (pin "C") (pinfunction "C_C") (pintype "passive"))
      (node (ref "R1_BAT") (pin "2") (pinfunction "2_2") (pintype "passive"))
    )
    (net (code "22") (name "Net-(D2-CATHODE)") (class "Default")
      (node (ref "C1_BAT1") (pin "1") (pinfunction "1_1") (pintype "passive"))
      (node (ref "D2") (pin "1") (pinfunction "CATHODE_1") (pintype "bidirectional"))
      (node (ref "IC4") (pin "1") (pinfunction "VIN_1") (pintype "bidirectional"))
      (node (ref "IC4") (pin "3") (pinfunction "CE_3") (pintype "bidirectional"))
      (node (ref "Q1") (pin "2") (pinfunction "S_2") (pintype "bidirectional"))
    )
    (net (code "23") (name "Net-(D3-A)") (class "Default")
      (node (ref "C4") (pin "1") (pinfunction "1_1") (pintype "passive"))
      (node (ref "D3") (pin "2") (pinfunction "A_2") (pintype "bidirectional"))
      (node (ref "D4") (pin "1") (pinfunction "K_1") (pintype "bidirectional"))
    )
    (net (code "24") (name "Net-(D7-CATHODE)") (class "Default")
      (node (ref "D7") (pin "1") (pinfunction "CATHODE_1") (pintype "bidirectional"))
      (node (ref "R1_CAPACITOR") (pin "1") (pinfunction "1_1") (pintype "passive"))
    )
    (net (code "25") (name "Net-(EPD_C1-Pad1)") (class "Default")
      (node (ref "EPD_C1") (pin "1") (pinfunction "1_1") (pintype "passive"))
      (node (ref "J1") (pin "4") (pinfunction "4_4") (pintype "bidirectional"))
    )
    (net (code "26") (name "Net-(EPD_C2-Pad1)") (class "Default")
      (node (ref "EPD_C2") (pin "1") (pinfunction "1_1") (pintype "passive"))
      (node (ref "J1") (pin "5") (pinfunction "5_5") (pintype "bidirectional"))
    )
    (net (code "27") (name "Net-(EPD_C6-Pad1)") (class "Default")
      (node (ref "EPD_C6") (pin "1") (pinfunction "1_1") (pintype "passive"))
      (node (ref "J1") (pin "18") (pinfunction "18_18") (pintype "bidirectional"))
    )
    (net (code "28") (name "Net-(EPD_C7-Pad1)") (class "Default")
      (node (ref "EPD_C7") (pin "1") (pinfunction "1_1") (pintype "passive"))
      (node (ref "J1") (pin "19") (pinfunction "19_19") (pintype "bidirectional"))
    )
    (net (code "29") (name "Net-(EPD_C8-Pad1)") (class "Default")
      (node (ref "EPD_C8") (pin "1") (pinfunction "1_1") (pintype "passive"))
      (node (ref "J1") (pin "20") (pinfunction "20_20") (pintype "bidirectional"))
    )
    (net (code "30") (name "Net-(EPD_C10-Pad1)") (class "Default")
      (node (ref "EPD_C10") (pin "1") (pinfunction "1_1") (pintype "passive"))
      (node (ref "J1") (pin "22") (pinfunction "22_22") (pintype "bidirectional"))
    )
    (net (code "31") (name "Net-(EPD_C12-Pad1)") (class "Default")
      (node (ref "EPD_C12") (pin "1") (pinfunction "1_1") (pintype "passive"))
      (node (ref "J1") (pin "24") (pinfunction "24_24") (pintype "bidirectional"))
    )
    (net (code "32") (name "Net-(IC1-CT)") (class "Default")
      (node (ref "C_DELAY") (pin "1") (pinfunction "1_1") (pintype "passive"))
      (node (ref "IC1") (pin "5") (pinfunction "CT_5") (pintype "bidirectional"))
    )
    (net (code "33") (name "Net-(J2-PadA5)") (class "Default")
      (node (ref "J2") (pin "A5") (pinfunction "A5_A5") (pintype "bidirectional"))
      (node (ref "R2-USB1") (pin "2") (pinfunction "2_2") (pintype "passive"))
    )
    (net (code "34") (name "Net-(J2-PadB5)") (class "Default")
      (node (ref "J2") (pin "B5") (pinfunction "B5_B5") (pintype "bidirectional"))
      (node (ref "R2-USB") (pin "1") (pinfunction "1_1") (pintype "passive"))
    )
    (net (code "35") (name "Net-(MCP73831-PROG)") (class "Default")
      (node (ref "MCP73831") (pin "5") (pinfunction "PROG_5") (pintype "input"))
      (node (ref "R2_BAT") (pin "2") (pinfunction "2_2") (pintype "passive"))
    )
    (net (code "36") (name "Net-(MCP73831-STAT)") (class "Default")
      (node (ref "MCP73831") (pin "1") (pinfunction "STAT_1") (pintype "output"))
      (node (ref "R1_BAT") (pin "1") (pinfunction "1_1") (pintype "passive"))
    )
    (net (code "37") (name "PREVGH") (class "Default")
      (node (ref "D5") (pin "1") (pinfunction "K_1") (pintype "bidirectional"))
      (node (ref "EPD_C9") (pin "1") (pinfunction "1_1") (pintype "passive"))
      (node (ref "J1") (pin "21") (pinfunction "21_21") (pintype "bidirectional"))
    )
    (net (code "38") (name "PREVGL") (class "Default")
      (node (ref "D4") (pin "2") (pinfunction "A_2") (pintype "bidirectional"))
      (node (ref "EPD_C11") (pin "1") (pinfunction "1_1") (pintype "passive"))
      (node (ref "J1") (pin "23") (pinfunction "23_23") (pintype "bidirectional"))
    )
    (net (code "39") (name "RESE") (class "Default")
      (node (ref "J1") (pin "3") (pinfunction "3_3") (pintype "bidirectional"))
      (node (ref "Q3") (pin "2") (pinfunction "S_2") (pintype "bidirectional"))
      (node (ref "R3") (pin "1") (pinfunction "1_1") (pintype "passive"))
    )
    (net (code "40") (name "RESE'") (class "Default")
      (node (ref "R2") (pin "2") (pinfunction "2_2") (pintype "passive"))
      (node (ref "R3") (pin "2") (pinfunction "2_2") (pintype "passive"))
      (node (ref "SJ1") (pin "2") (pinfunction "2_2") (pintype "passive"))
    )
    (net (code "41") (name "RESET") (class "Default")
      (node (ref "C5") (pin "1") (pinfunction "1_1") (pintype "passive"))
      (node (ref "IC1") (pin "1") (pinfunction "VOUT_1") (pintype "bidirectional"))
      (node (ref "RESET_BUTTON") (pin "3") (pinfunction "3_3") (pintype "passive"))
      (node (ref "RESET_BUTTON") (pin "4") (pinfunction "4_4") (pintype "passive"))
      (node (ref "R_RESET") (pin "2") (pinfunction "2_2") (pintype "passive"))
      (node (ref "U2") (pin "3") (pinfunction "EN_3") (pintype "input"))
    )
    (net (code "42") (name "RTC_RST") (class "Default")
      (node (ref "U2") (pin "16") (pinfunction "IO18_16") (pintype "bidirectional"))
      (node (ref "U3") (pin "4") (pinfunction "~{RST}_4") (pintype "input"))
    )
    (net (code "43") (name "RX") (class "Default")
      (node (ref "TP2") (pin "TP") (pinfunction "TP_TP") (pintype "input"))
      (node (ref "U2") (pin "24") (pinfunction "RXD0/GPIO17_24") (pintype "bidirectional"))
    )
    (net (code "44") (name "SCK") (class "Default")
      (node (ref "D10") (pin "2") (pinfunction "2_2") (pintype "passive"))
      (node (ref "J1") (pin "13") (pinfunction "13_13") (pintype "bidirectional"))
      (node (ref "J4") (pin "P5") (pinfunction "CLK_P5") (pintype "bidirectional"))
      (node (ref "R6") (pin "1") (pinfunction "1_1") (pintype "passive"))
      (node (ref "TP8") (pin "TP") (pinfunction "TP_TP") (pintype "input"))
      (node (ref "U1") (pin "6") (pinfunction "CLK_6") (pintype "input"))
      (node (ref "U2") (pin "6") (pinfunction "IO6_6") (pintype "bidirectional"))
    )
    (net (code "45") (name "SCL") (class "Default")
      (node (ref "J3") (pin "4") (pinfunction "4_4") (pintype "passive"))
      (node (ref "R2_PINH") (pin "1") (pinfunction "1_1") (pintype "passive"))
      (node (ref "SENSOR2") (pin "4") (pinfunction "SCK_4") (pintype "input"))
      (node (ref "U2") (pin "20") (pinfunction "IO22_20") (pintype "bidirectional"))
      (node (ref "U3") (pin "16") (pinfunction "SCL_16") (pintype "input"))
      (node (ref "U4") (pin "7") (pinfunction "SCL_7") (pintype "input"))
    )
    (net (code "46") (name "SDA") (class "Default")
      (node (ref "J3") (pin "3") (pinfunction "3_3") (pintype "passive"))
      (node (ref "R1_PINH") (pin "1") (pinfunction "1_1") (pintype "passive"))
      (node (ref "SENSOR2") (pin "3") (pinfunction "SDI_3") (pintype "bidirectional"))
      (node (ref "U2") (pin "19") (pinfunction "IO21_19") (pintype "bidirectional"))
      (node (ref "U3") (pin "15") (pinfunction "SDA_15") (pintype "bidirectional"))
      (node (ref "U4") (pin "8") (pinfunction "SDA_8") (pintype "bidirectional"))
    )
    (net (code "47") (name "SRC") (class "Default")
      (node (ref "C4") (pin "2") (pinfunction "2_2") (pintype "passive"))
      (node (ref "D5") (pin "2") (pinfunction "A_2") (pintype "bidirectional"))
      (node (ref "L1") (pin "1") (pinfunction "1_1") (pintype "passive"))
      (node (ref "Q3") (pin "3") (pinfunction "D_3") (pintype "bidirectional"))
    )
    (net (code "48") (name "SS_SD") (class "Default")
      (node (ref "D8") (pin "2") (pinfunction "2_2") (pintype "passive"))
      (node (ref "J4") (pin "P2") (pinfunction "CD/DAT3_P2") (pintype "bidirectional"))
      (node (ref "R10") (pin "1") (pinfunction "1_1") (pintype "passive"))
      (node (ref "U2") (pin "4") (pinfunction "IO4_4") (pintype "bidirectional"))
    )
    (net (code "49") (name "TX") (class "Default")
      (node (ref "TP1") (pin "TP") (pinfunction "TP_TP") (pintype "input"))
      (node (ref "U2") (pin "25") (pinfunction "TXD0/GPIO16_25") (pintype "bidirectional"))
    )
    (net (code "50") (name "USB_D+") (class "Default")
      (node (ref "D1") (pin "1") (pinfunction "I/O1_1_1") (pintype "bidirectional"))
      (node (ref "U2") (pin "14") (pinfunction "IO13_14") (pintype "bidirectional"))
    )
    (net (code "51") (name "USB_D-") (class "Default")
      (node (ref "D1") (pin "3") (pinfunction "I/O2_1_3") (pintype "bidirectional"))
      (node (ref "U2") (pin "13") (pinfunction "IO12_13") (pintype "bidirectional"))
    )
    (net (code "52") (name "VBAT") (class "Default")
      (node (ref "C2_BAT") (pin "1") (pinfunction "1_1") (pintype "passive"))
      (node (ref "MCP73831") (pin "3") (pinfunction "VBAT_3") (pintype "power_in"))
      (node (ref "Q1") (pin "3") (pinfunction "D_3") (pintype "bidirectional"))
      (node (ref "TP3") (pin "TP") (pinfunction "TP_TP") (pintype "input"))
      (node (ref "U4") (pin "2") (pinfunction "CELL_2") (pintype "power_in"))
      (node (ref "U4") (pin "3") (pinfunction "VDD_3") (pintype "power_in"))
    )
    (net (code "53") (name "VBUS") (class "Default")
      (node (ref "C1_BAT") (pin "1") (pinfunction "1_1") (pintype "passive"))
      (node (ref "C4_USB") (pin "1") (pinfunction "1_1") (pintype "passive"))
      (node (ref "C5_USB") (pin "1") (pinfunction "1_1") (pintype "passive"))
      (node (ref "CHG_LED") (pin "A") (pinfunction "A_A") (pintype "passive"))
      (node (ref "D1") (pin "5") (pinfunction "VBUS_5") (pintype "bidirectional"))
      (node (ref "D2") (pin "2") (pinfunction "ANODE_2") (pintype "bidirectional"))
      (node (ref "MCP73831") (pin "4") (pinfunction "VIN_4") (pintype "power_in"))
      (node (ref "PFMF.050.1") (pin "2") (pinfunction "2_2") (pintype "passive"))
      (node (ref "Q1") (pin "1") (pinfunction "G_1") (pintype "bidirectional"))
      (node (ref "R1_PWRUSB") (pin "2") (pinfunction "2_2") (pintype "passive"))
      (node (ref "TP14") (pin "TP") (pinfunction "TP_TP") (pintype "input"))
    )
    (net (code "54") (name "VRTC") (class "Default")
      (node (ref "C10_SUPERCAP") (pin "2") (pinfunction "2_2") (pintype "passive"))
      (node (ref "C8") (pin "1") (pinfunction "1_1") (pintype "passive"))
      (node (ref "R1_CAPACITOR") (pin "2") (pinfunction "2_2") (pintype "passive"))
      (node (ref "U3") (pin "14") (pinfunction "VBAT_14") (pintype "power_in"))
    )
    (net (code "55") (name "VUSB") (class "Default")
      (node (ref "J2") (pin "A4") (pinfunction "A4_A4") (pintype "bidirectional"))
      (node (ref "J2") (pin "A9") (pinfunction "A9_A9") (pintype "bidirectional"))
      (node (ref "J2") (pin "B4") (pinfunction "B4_B4") (pintype "bidirectional"))
      (node (ref "J2") (pin "B9") (pinfunction "B9_B9") (pintype "bidirectional"))
      (node (ref "PFMF.050.1") (pin "1") (pinfunction "1_1") (pintype "passive"))
    )
    (net (code "56") (name "unconnected-(IC1-NC-Pad4)") (class "Default")
      (node (ref "IC1") (pin "4") (pinfunction "NC_4") (pintype "no_connect"))
    )
    (net (code "57") (name "unconnected-(IC4-NC-Pad4)") (class "Default")
      (node (ref "IC4") (pin "4") (pinfunction "NC_4") (pintype "no_connect"))
    )
    (net (code "58") (name "unconnected-(J1-Pad1)") (class "Default")
      (node (ref "J1") (pin "1") (pinfunction "1_1") (pintype "bidirectional"))
    )
    (net (code "59") (name "unconnected-(J1-Pad6)") (class "Default")
      (node (ref "J1") (pin "6") (pinfunction "6_6") (pintype "bidirectional"))
    )
    (net (code "60") (name "unconnected-(J1-Pad7)") (class "Default")
      (node (ref "J1") (pin "7") (pinfunction "7_7") (pintype "bidirectional"))
    )
    (net (code "61") (name "unconnected-(J2-PadA8)") (class "Default")
      (node (ref "J2") (pin "A8") (pinfunction "A8_A8") (pintype "bidirectional"))
    )
    (net (code "62") (name "unconnected-(J2-PadB8)") (class "Default")
      (node (ref "J2") (pin "B8") (pinfunction "B8_B8") (pintype "bidirectional"))
    )
    (net (code "63") (name "unconnected-(J4-DAT1-PadP8)") (class "Default")
      (node (ref "J4") (pin "P8") (pinfunction "DAT1_P8") (pintype "bidirectional"))
    )
    (net (code "64") (name "unconnected-(J4-DAT2-PadP1)") (class "Default")
      (node (ref "J4") (pin "P1") (pinfunction "DAT2_P1") (pintype "bidirectional"))
    )
    (net (code "65") (name "unconnected-(J4-DETECTION_1-PadS1)") (class "Default")
      (node (ref "J4") (pin "S1") (pinfunction "DETECTION_1_S1") (pintype "bidirectional"))
    )
    (net (code "66") (name "unconnected-(J4-DETECTION_2-PadS2)") (class "Default")
      (node (ref "J4") (pin "S2") (pinfunction "DETECTION_2_S2") (pintype "bidirectional"))
    )
    (net (code "67") (name "unconnected-(U2-NC-Pad22)") (class "Default")
      (node (ref "U2") (pin "22") (pinfunction "NC_22") (pintype "no_connect"))
    )
    (net (code "68") (name "unconnected-(U4-~{ALERT}-Pad5)") (class "Default")
      (node (ref "U4") (pin "5") (pinfunction "~{ALERT}_5") (pintype "output"))
    )
  )
)
